# cooling_shield.net
KiCad netlist of a schematic drawn in Altium Designer
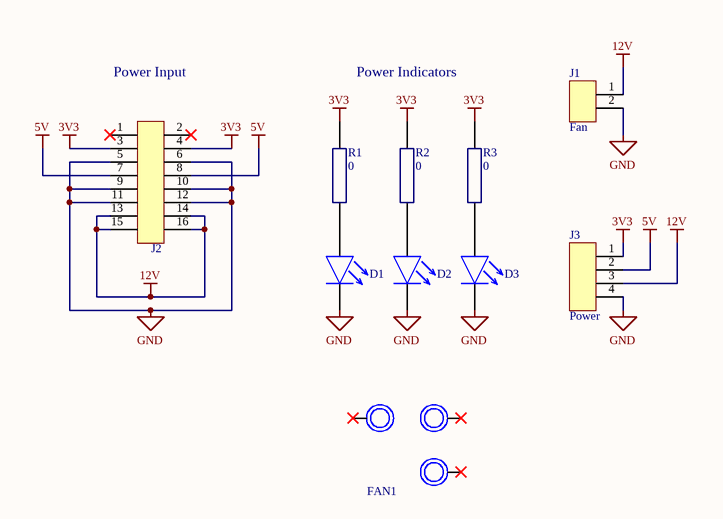
[diagram p0: cooling_shield.SchDoc]

(export (version "E")
  (design (tool "Eeschema 10.0.6"))
  (components
    (comp (ref "D1")
      (value "XZFBB45S-9")
      (footprint "PLCC-2")
      (description "LED BLUE CLEAR 2PLCC SMD")
      (fields (field (name "MANUFACTURER") "SunLED"))
      (libsource (lib "AMMDK Parts") (part "XZFBB45S-9"))
    )
    (comp (ref "D2")
      (value "XZFBB45S-9")
      (footprint "PLCC-2")
      (description "LED BLUE CLEAR 2PLCC SMD")
      (fields (field (name "MANUFACTURER") "SunLED"))
      (libsource (lib "AMMDK Parts") (part "XZFBB45S-9"))
    )
    (comp (ref "D3")
      (value "XZFBB45S-9")
      (footprint "PLCC-2")
      (description "LED BLUE CLEAR 2PLCC SMD")
      (fields (field (name "MANUFACTURER") "SunLED"))
      (libsource (lib "AMMDK Parts") (part "XZFBB45S-9"))
    )
    (comp (ref "FAN1")
      (value "fan")
      (footprint "fan")
      (description "RND STANDOFF M2.5X0.45 STEEL 8MM")
      (fields
        (field (name "MANUFACTURER") "Wurth Electronics")
        (field (name "MANUFACTURER PART NUMBER") "9774080151R")
      )
      (libsource (lib "AMMDK Parts") (part "fan"))
    )
    (comp (ref "J1")
      (value "Fan")
      (footprint "1718561002")
      (description "Headers & Wire Housings KK Hdr Vrt 2 Ckt 2.54mm Pitch 15um Au")
      (fields (field (name "MANUFACTURER") "Molex") (field (name "MANUFACTURER PART NUMBER") "1718561002"))
      (libsource (lib "AMMDK Parts") (part "1718561002"))
    )
    (comp (ref "J2")
      (value "DF11-16DP-2DSA(01)")
      (footprint "DF11-16DP-2DSA(01)_FLIP")
      (description "Headers & Wire Housings 2MM V PCB HEADER 16P DR THRU-HOLE GLD")
      (fields (field (name "MANUFACTURER") "Hirose Connector"))
      (libsource (lib "AMMDK Parts") (part "DF11-16DP-2DSA(01)"))
    )
    (comp (ref "J3")
      (value "Power")
      (footprint "282834-4")
      (description "4 Position Wire to Board Terminal Block")
      (libsource (lib "AMMDK Parts") (part "282834-4"))
    )
    (comp (ref "R1")
      (value "0")
      (footprint "RESC2012X07N_SAMSUNG")
      (description "Res Thick Film 0805 0 Ohm Molded SMD T/R")
      (fields
        (field (name "MANUFACTURER") "Samsung")
        (field (name "MANUFACTURER PART NUMBER") "RC2012J000CS")
      )
      (libsource (lib "AMMDK Parts") (part "RC2012J000CS"))
    )
    (comp (ref "R2")
      (value "0")
      (footprint "RESC2012X07N_SAMSUNG")
      (description "Res Thick Film 0805 0 Ohm Molded SMD T/R")
      (fields
        (field (name "MANUFACTURER") "Samsung")
        (field (name "MANUFACTURER PART NUMBER") "RC2012J000CS")
      )
      (libsource (lib "AMMDK Parts") (part "RC2012J000CS"))
    )
    (comp (ref "R3")
      (value "0")
      (footprint "RESC2012X07N_SAMSUNG")
      (description "Res Thick Film 0805 0 Ohm Molded SMD T/R")
      (fields
        (field (name "MANUFACTURER") "Samsung")
        (field (name "MANUFACTURER PART NUMBER") "RC2012J000CS")
      )
      (libsource (lib "AMMDK Parts") (part "RC2012J000CS"))
    )
  )
  (nets
    (net (code "1") (name "3V3") (class "Default")
      (node (ref "J2") (pin "3") (pintype "power_in"))
      (node (ref "J2") (pin "4") (pintype "power_in"))
      (node (ref "J3") (pin "1") (pintype "passive"))
      (node (ref "R1") (pin "2") (pinfunction "2_2") (pintype "passive"))
      (node (ref "R2") (pin "2") (pinfunction "2_2") (pintype "passive"))
      (node (ref "R3") (pin "2") (pinfunction "2_2") (pintype "passive"))
    )
    (net (code "2") (name "5V") (class "Default")
      (node (ref "J2") (pin "7") (pintype "power_in"))
      (node (ref "J2") (pin "8") (pintype "power_in"))
      (node (ref "J3") (pin "2") (pintype "passive"))
    )
    (net (code "3") (name "12V") (class "Default")
      (node (ref "J1") (pin "1") (pintype "passive"))
      (node (ref "J2") (pin "13") (pintype "power_in"))
      (node (ref "J2") (pin "14") (pintype "power_in"))
      (node (ref "J2") (pin "15") (pintype "power_in"))
      (node (ref "J2") (pin "16") (pintype "power_in"))
      (node (ref "J3") (pin "3") (pintype "passive"))
    )
    (net (code "4") (name "GND") (class "Default")
      (node (ref "D1") (pin "2") (pinfunction "2_2") (pintype "passive"))
      (node (ref "D2") (pin "2") (pinfunction "2_2") (pintype "passive"))
      (node (ref "D3") (pin "2") (pinfunction "2_2") (pintype "passive"))
      (node (ref "J1") (pin "2") (pintype "passive"))
      (node (ref "J2") (pin "10") (pintype "power_in"))
      (node (ref "J2") (pin "11") (pintype "power_in"))
      (node (ref "J2") (pin "12") (pintype "power_in"))
      (node (ref "J2") (pin "5") (pintype "power_in"))
      (node (ref "J2") (pin "6") (pintype "power_in"))
      (node (ref "J2") (pin "9") (pintype "power_in"))
      (node (ref "J3") (pin "4") (pintype "passive"))
    )
    (net (code "5") (name "Net-(D1-Pad1)") (class "Default")
      (node (ref "D1") (pin "1") (pinfunction "1_1") (pintype "passive"))
      (node (ref "R1") (pin "1") (pinfunction "1_1") (pintype "passive"))
    )
    (net (code "6") (name "Net-(D2-Pad1)") (class "Default")
      (node (ref "D2") (pin "1") (pinfunction "1_1") (pintype "passive"))
      (node (ref "R2") (pin "1") (pinfunction "1_1") (pintype "passive"))
    )
    (net (code "7") (name "Net-(D3-Pad1)") (class "Default")
      (node (ref "D3") (pin "1") (pinfunction "1_1") (pintype "passive"))
      (node (ref "R3") (pin "1") (pinfunction "1_1") (pintype "passive"))
    )
    (net (code "8") (name "unconnected-(FAN1-Pad1)") (class "Default")
      (node (ref "FAN1") (pin "1") (pinfunction "1_1") (pintype "passive+no_connect"))
    )
    (net (code "9") (name "unconnected-(FAN1-Pad2)") (class "Default")
      (node (ref "FAN1") (pin "2") (pinfunction "2_2") (pintype "passive+no_connect"))
    )
    (net (code "10") (name "unconnected-(FAN1-Pad3)") (class "Default")
      (node (ref "FAN1") (pin "3") (pinfunction "3_3") (pintype "passive+no_connect"))
    )
    (net (code "11") (name "unconnected-(J2-Pad1)") (class "Default")
      (node (ref "J2") (pin "1") (pintype "power_in+no_connect"))
    )
    (net (code "12") (name "unconnected-(J2-Pad2)") (class "Default")
      (node (ref "J2") (pin "2") (pintype "power_in+no_connect"))
    )
  )
)
